# Qwiic_TMP117.net
KiCad netlist of a schematic drawn in EAGLE
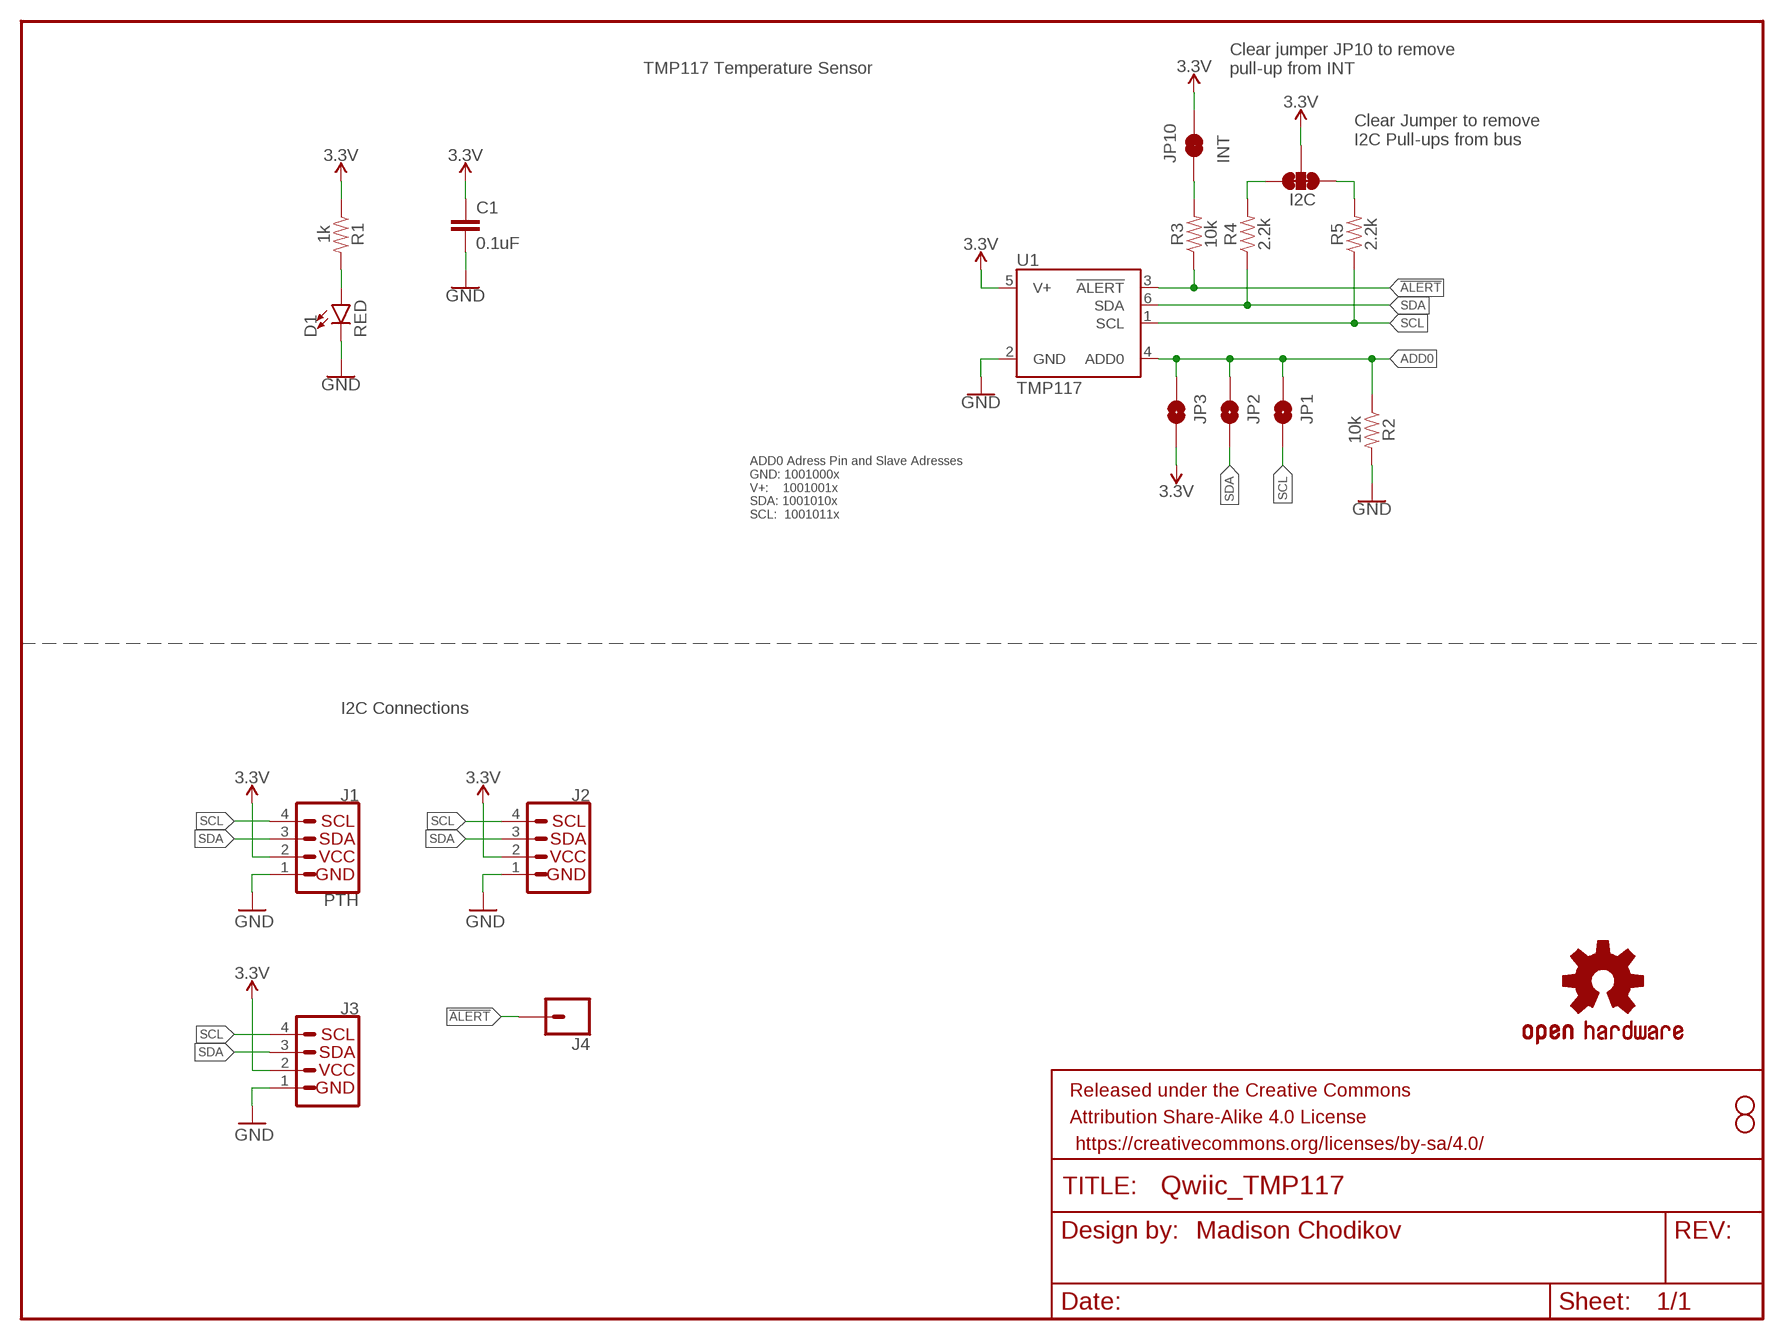
[diagram p0: schematic, sheet 1]

(export (version "E")
  (design (tool "Eeschema 10.0.6"))
  (components
    (comp (ref "C1")
      (value "0.1uF")
      (footprint "eagle-import:0603")
      (libsource (lib "eagle-import") (part "0.1UF-0603-25V-(+80/-20%)"))
    )
    (comp (ref "D1")
      (value "RED")
      (footprint "eagle-import:LED-0603")
      (libsource (lib "eagle-import") (part "LED-RED0603"))
    )
    (comp (ref "FRAME1")
      (value "FRAME-LETTER")
      (footprint "eagle-import:CREATIVE_COMMONS")
      (libsource (lib "eagle-import") (part "FRAME-LETTER"))
    )
    (comp (ref "I2C")
      (value "JUMPER-SMT_3_2-NC_TRACE_SILK")
      (footprint "eagle-import:SMT-JUMPER_3_2-NC_TRACE_SILK")
      (libsource (lib "eagle-import") (part "JUMPER-SMT_3_2-NC_TRACE_SILK"))
    )
    (comp (ref "J1")
      (value "PTH")
      (footprint "eagle-import:1X04_NO_SILK")
      (libsource (lib "eagle-import") (part "I2C_STANDARD_NO_SILK"))
    )
    (comp (ref "J2")
      (value "QWIIC_CONNECTORJS-1MM")
      (footprint "eagle-import:JST04_1MM_RA")
      (libsource (lib "eagle-import") (part "QWIIC_CONNECTORJS-1MM"))
    )
    (comp (ref "J3")
      (value "QWIIC_CONNECTORJS-1MM")
      (footprint "eagle-import:JST04_1MM_RA")
      (libsource (lib "eagle-import") (part "QWIIC_CONNECTORJS-1MM"))
    )
    (comp (ref "J4")
      (value "CONN_01PTH_NO_SILK_YES_STOP")
      (footprint "eagle-import:1X01_NO_SILK")
      (libsource (lib "eagle-import") (part "CONN_01PTH_NO_SILK_YES_STOP"))
    )
    (comp (ref "JP1")
      (value "JUMPER-SMT_2_NO_SILK")
      (footprint "eagle-import:SMT-JUMPER_2_NO_SILK")
      (libsource (lib "eagle-import") (part "JUMPER-SMT_2_NO_SILK"))
    )
    (comp (ref "JP2")
      (value "JUMPER-SMT_2_NO_SILK")
      (footprint "eagle-import:SMT-JUMPER_2_NO_SILK")
      (libsource (lib "eagle-import") (part "JUMPER-SMT_2_NO_SILK"))
    )
    (comp (ref "JP3")
      (value "JUMPER-SMT_2_NO_SILK")
      (footprint "eagle-import:SMT-JUMPER_2_NO_SILK")
      (libsource (lib "eagle-import") (part "JUMPER-SMT_2_NO_SILK"))
    )
    (comp (ref "JP8")
      (value "STAND-OFF")
      (footprint "eagle-import:STAND-OFF")
      (libsource (lib "eagle-import") (part "STAND-OFF"))
    )
    (comp (ref "JP9")
      (value "STAND-OFF")
      (footprint "eagle-import:STAND-OFF")
      (libsource (lib "eagle-import") (part "STAND-OFF"))
    )
    (comp (ref "JP10")
      (value "INT")
      (footprint "eagle-import:PAD-JUMPER-2-NC_BY_TRACE_YES_SILK")
      (libsource (lib "eagle-import") (part "JUMPER-PAD-2-NC_BY_TRACE"))
    )
    (comp (ref "LOGO1")
      (value "OSHW-LOGOMINI")
      (footprint "eagle-import:OSHW-LOGO-MINI")
      (libsource (lib "eagle-import") (part "OSHW-LOGOMINI"))
    )
    (comp (ref "R1")
      (value "1k")
      (footprint "eagle-import:0603")
      (libsource (lib "eagle-import") (part "1KOHM-0603-1/10W-1%"))
    )
    (comp (ref "R2")
      (value "10k")
      (footprint "eagle-import:0603")
      (libsource (lib "eagle-import") (part "10KOHM-0603-1/10W-1%"))
    )
    (comp (ref "R3")
      (value "10k")
      (footprint "eagle-import:0603")
      (libsource (lib "eagle-import") (part "10KOHM-0603-1/10W-1%"))
    )
    (comp (ref "R4")
      (value "2.2k")
      (footprint "eagle-import:0603")
      (libsource (lib "eagle-import") (part "2.2KOHM-0603-1/10W-1%"))
    )
    (comp (ref "R5")
      (value "2.2k")
      (footprint "eagle-import:0603")
      (libsource (lib "eagle-import") (part "2.2KOHM-0603-1/10W-1%"))
    )
    (comp (ref "U1")
      (value "TMP117")
      (footprint "eagle-import:TMP117")
      (libsource (lib "eagle-import") (part "TMP117"))
    )
  )
  (nets
    (net (code "1") (name "/~{ALERT}") (class "Default")
      (node (ref "J4") (pin "1") (pinfunction "1_1") (pintype "passive"))
      (node (ref "R3") (pin "1") (pinfunction "1_1") (pintype "passive"))
      (node (ref "U1") (pin "3") (pinfunction "~{ALERT}_3") (pintype "bidirectional"))
    )
    (net (code "2") (name "3.3V") (class "Default")
      (node (ref "C1") (pin "1") (pinfunction "1_1") (pintype "passive"))
      (node (ref "I2C") (pin "2") (pinfunction "2_2") (pintype "passive"))
      (node (ref "J1") (pin "2") (pinfunction "VCC_2") (pintype "power_in"))
      (node (ref "J2") (pin "2") (pinfunction "2_2") (pintype "power_in"))
      (node (ref "J3") (pin "2") (pinfunction "2_2") (pintype "power_in"))
      (node (ref "JP10") (pin "2") (pinfunction "2_2") (pintype "passive"))
      (node (ref "JP3") (pin "2") (pinfunction "2_2") (pintype "passive"))
      (node (ref "R1") (pin "1") (pinfunction "1_1") (pintype "passive"))
      (node (ref "U1") (pin "5") (pinfunction "V+_5") (pintype "power_in"))
    )
    (net (code "3") (name "ADD0") (class "Default")
      (node (ref "JP1") (pin "1") (pinfunction "1_1") (pintype "passive"))
      (node (ref "JP2") (pin "1") (pinfunction "1_1") (pintype "passive"))
      (node (ref "JP3") (pin "1") (pinfunction "1_1") (pintype "passive"))
      (node (ref "R2") (pin "1") (pinfunction "1_1") (pintype "passive"))
      (node (ref "U1") (pin "4") (pinfunction "ADD0_4") (pintype "bidirectional"))
    )
    (net (code "4") (name "GND") (class "Default")
      (node (ref "C1") (pin "2") (pinfunction "2_2") (pintype "passive"))
      (node (ref "D1") (pin "C") (pinfunction "C_C") (pintype "passive"))
      (node (ref "J1") (pin "1") (pinfunction "GND_1") (pintype "power_in"))
      (node (ref "J2") (pin "1") (pinfunction "1_1") (pintype "power_in"))
      (node (ref "J3") (pin "1") (pinfunction "1_1") (pintype "power_in"))
      (node (ref "R2") (pin "2") (pinfunction "2_2") (pintype "passive"))
      (node (ref "U1") (pin "2") (pinfunction "GND_2") (pintype "bidirectional"))
    )
    (net (code "5") (name "Net-(D1-PadA)") (class "Default")
      (node (ref "D1") (pin "A") (pinfunction "A_A") (pintype "passive"))
      (node (ref "R1") (pin "2") (pinfunction "2_2") (pintype "passive"))
    )
    (net (code "6") (name "Net-(I2C-Pad1)") (class "Default")
      (node (ref "I2C") (pin "1") (pinfunction "1_1") (pintype "passive"))
      (node (ref "R5") (pin "2") (pinfunction "2_2") (pintype "passive"))
    )
    (net (code "7") (name "Net-(I2C-Pad3)") (class "Default")
      (node (ref "I2C") (pin "3") (pinfunction "3_3") (pintype "passive"))
      (node (ref "R4") (pin "2") (pinfunction "2_2") (pintype "passive"))
    )
    (net (code "8") (name "Net-(JP10-Pad1)") (class "Default")
      (node (ref "JP10") (pin "1") (pinfunction "1_1") (pintype "passive"))
      (node (ref "R3") (pin "2") (pinfunction "2_2") (pintype "passive"))
    )
    (net (code "9") (name "SCL") (class "Default")
      (node (ref "J1") (pin "4") (pinfunction "SCL_4") (pintype "passive"))
      (node (ref "J2") (pin "4") (pinfunction "4_4") (pintype "passive"))
      (node (ref "J3") (pin "4") (pinfunction "4_4") (pintype "passive"))
      (node (ref "JP1") (pin "2") (pinfunction "2_2") (pintype "passive"))
      (node (ref "R5") (pin "1") (pinfunction "1_1") (pintype "passive"))
      (node (ref "U1") (pin "1") (pinfunction "SCL_1") (pintype "bidirectional"))
    )
    (net (code "10") (name "SDA") (class "Default")
      (node (ref "J1") (pin "3") (pinfunction "SDA_3") (pintype "passive"))
      (node (ref "J2") (pin "3") (pinfunction "3_3") (pintype "passive"))
      (node (ref "J3") (pin "3") (pinfunction "3_3") (pintype "passive"))
      (node (ref "JP2") (pin "2") (pinfunction "2_2") (pintype "passive"))
      (node (ref "R4") (pin "1") (pinfunction "1_1") (pintype "passive"))
      (node (ref "U1") (pin "6") (pinfunction "SDA_6") (pintype "bidirectional"))
    )
  )
)
